# 19.net
KiCad netlist of a schematic drawn in Altium Designer
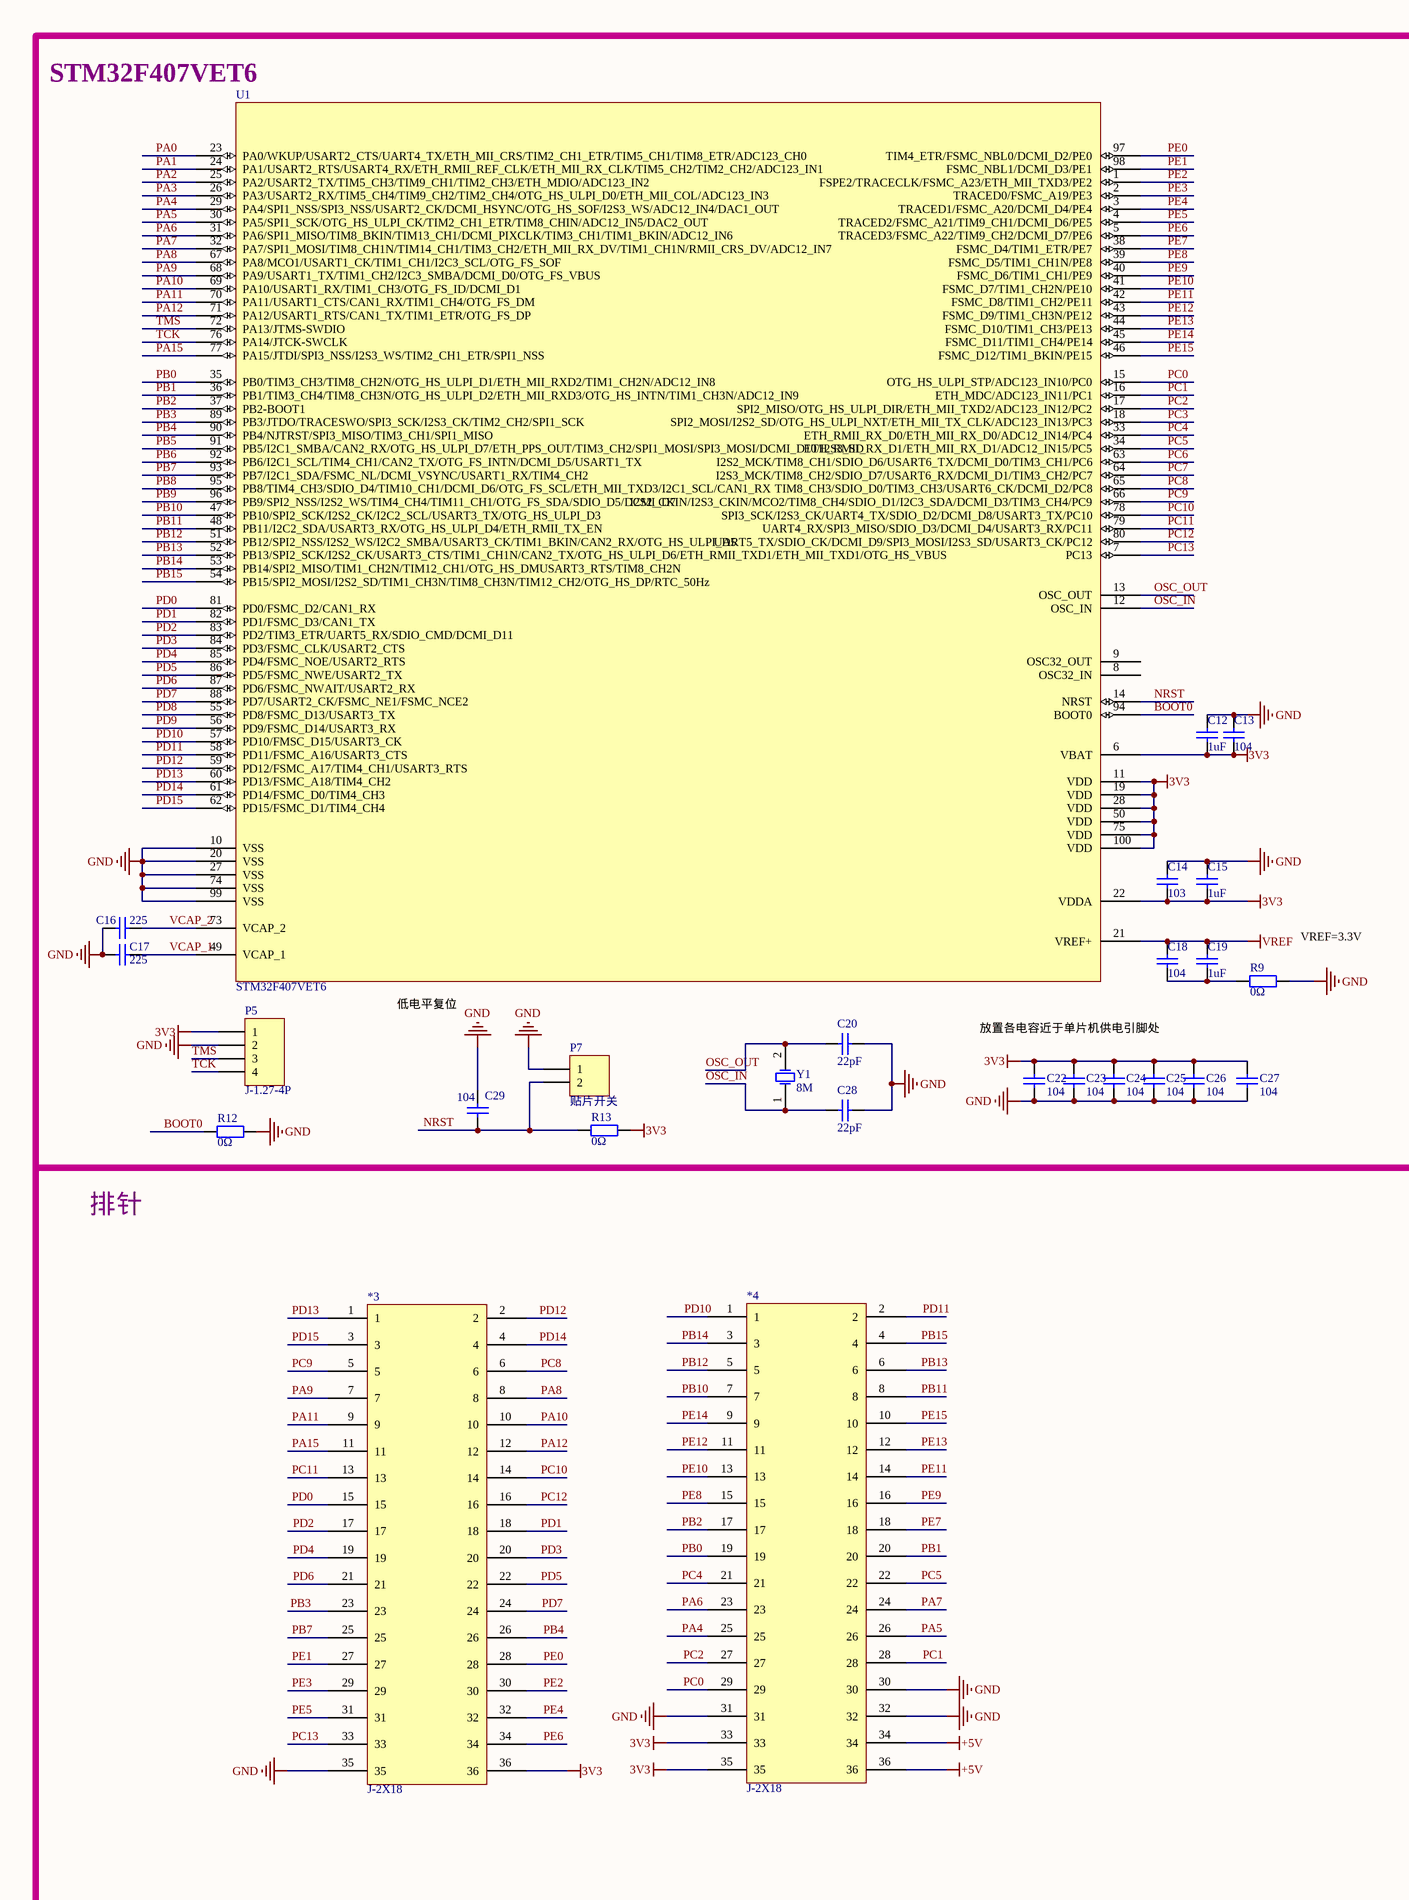
[diagram p0: 19主控.SchDoc, left]
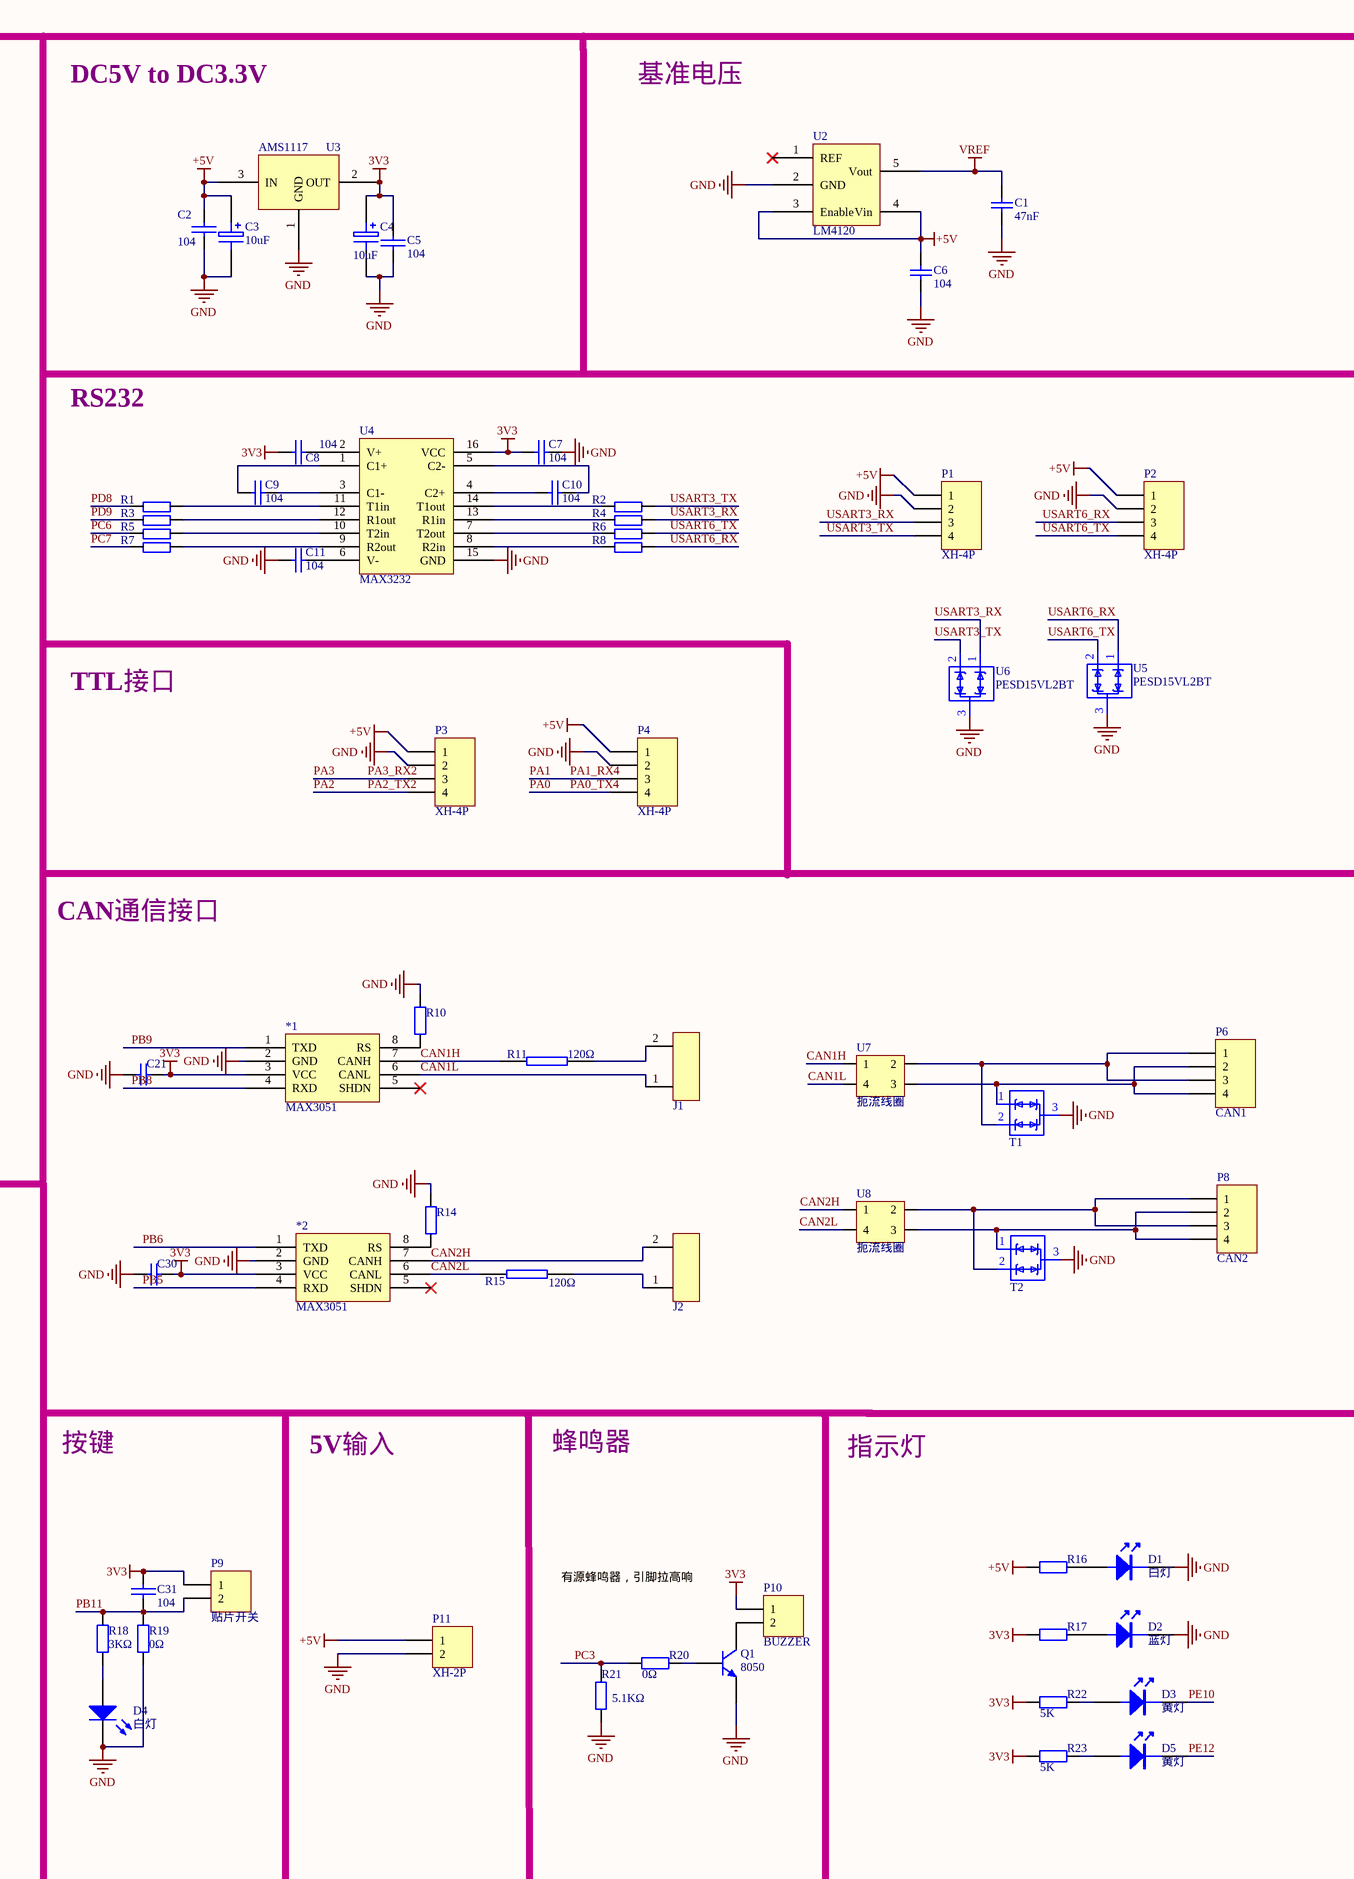
[diagram p1: 19主控.SchDoc, right]

(export (version "E")
  (design (tool "Eeschema 10.0.6"))
  (components
    (comp (ref "*1")
      (value "MAX3051")
      (footprint "SOT-23-8")
      (libsource (lib "ACTION原理图库") (part "MAX3051EKA+T"))
    )
    (comp (ref "*2")
      (value "MAX3051")
      (footprint "SOT-23-8")
      (libsource (lib "ACTION原理图库") (part "MAX3051EKA+T"))
    )
    (comp (ref "*3") (value "J-2X18") (footprint "HDR2X18 排座") (libsource (lib "ACTION原理图库") (part "J-2X18")))
    (comp (ref "*4") (value "J-2X18") (footprint "HDR2X18 排座") (libsource (lib "ACTION原理图库") (part "J-2X18")))
    (comp (ref "C1")
      (value "47nF")
      (footprint "0603_C")
      (description "Capacitor")
      (fields (field (name "PUBLISHER") "Altium Limited"))
      (libsource (lib "Miscellaneous Devices") (part "Cap"))
    )
    (comp (ref "C2")
      (value "104")
      (footprint "0603_C")
      (description "Capacitor")
      (libsource (lib "*") (part "CAP"))
    )
    (comp (ref "C3")
      (value "10uF")
      (footprint "0603_C")
      (description "Electrolytic Capacitor")
      (libsource (lib "*") (part "ELECTRO1"))
    )
    (comp (ref "C4")
      (value "10uF")
      (footprint "0603_C")
      (description "Electrolytic Capacitor")
      (libsource (lib "*") (part "ELECTRO1"))
    )
    (comp (ref "C5")
      (value "104")
      (footprint "0603_C")
      (description "Capacitor")
      (libsource (lib "*") (part "CAP"))
    )
    (comp (ref "C6")
      (value "104")
      (footprint "0603_C")
      (description "Capacitor")
      (fields (field (name "PUBLISHER") "Altium Limited"))
      (libsource (lib "Miscellaneous Devices") (part "Cap"))
    )
    (comp (ref "C7")
      (value "104")
      (footprint "0603_C")
      (description "Capacitor")
      (libsource (lib "*") (part "CAP"))
    )
    (comp (ref "C8")
      (value "104")
      (footprint "0603_C")
      (description "Capacitor")
      (libsource (lib "*") (part "CAP"))
    )
    (comp (ref "C9")
      (value "104")
      (footprint "0603_C")
      (description "Capacitor")
      (libsource (lib "*") (part "CAP"))
    )
    (comp (ref "C10")
      (value "104")
      (footprint "0603_C")
      (description "Capacitor")
      (libsource (lib "*") (part "CAP"))
    )
    (comp (ref "C11")
      (value "104")
      (footprint "0603_C")
      (description "Capacitor")
      (libsource (lib "*") (part "CAP"))
    )
    (comp (ref "C12")
      (value "1uF")
      (footprint "0603_C")
      (description "Capacitor")
      (fields (field (name "PUBLISHER") "Altium Limited"))
      (libsource (lib "Miscellaneous Devices") (part "Cap"))
    )
    (comp (ref "C13")
      (value "104")
      (footprint "0603_C")
      (description "Capacitor")
      (fields (field (name "PUBLISHER") "Altium Limited"))
      (libsource (lib "Miscellaneous Devices") (part "Cap"))
    )
    (comp (ref "C14")
      (value "103")
      (footprint "0603_C")
      (description "Capacitor")
      (fields (field (name "PUBLISHER") "Altium Limited"))
      (libsource (lib "Miscellaneous Devices") (part "Cap"))
    )
    (comp (ref "C15")
      (value "1uF")
      (footprint "0603_C")
      (description "Capacitor")
      (fields (field (name "PUBLISHER") "Altium Limited"))
      (libsource (lib "Miscellaneous Devices") (part "Cap"))
    )
    (comp (ref "C16")
      (value "225")
      (footprint "0603_C")
      (description "Capacitor")
      (fields (field (name "PUBLISHER") "Altium Limited"))
      (libsource (lib "Miscellaneous Devices") (part "Cap"))
    )
    (comp (ref "C17")
      (value "225")
      (footprint "0603_C")
      (description "Capacitor")
      (fields (field (name "PUBLISHER") "Altium Limited"))
      (libsource (lib "Miscellaneous Devices") (part "Cap"))
    )
    (comp (ref "C18")
      (value "104")
      (footprint "0603_C")
      (description "Capacitor")
      (fields (field (name "PUBLISHER") "Altium Limited"))
      (libsource (lib "Miscellaneous Devices") (part "Cap"))
    )
    (comp (ref "C19")
      (value "1uF")
      (footprint "0603_C")
      (description "Capacitor")
      (fields (field (name "PUBLISHER") "Altium Limited"))
      (libsource (lib "Miscellaneous Devices") (part "Cap"))
    )
    (comp (ref "C20")
      (value "22pF")
      (footprint "0603_C")
      (description "Capacitor")
      (fields (field (name "PUBLISHER") "Altium Limited"))
      (libsource (lib "Miscellaneous Devices") (part "Cap"))
    )
    (comp (ref "C21")
      (value "104")
      (footprint "0603_C")
      (description "贴片电容")
      (libsource (lib "Cap0603") (part "0603 100nF (104) 10% 50V"))
    )
    (comp (ref "C22")
      (value "104")
      (footprint "0603_C")
      (description "Capacitor")
      (fields (field (name "PUBLISHER") "Altium Limited"))
      (libsource (lib "Miscellaneous Devices") (part "Cap"))
    )
    (comp (ref "C23")
      (value "104")
      (footprint "0603_C")
      (description "Capacitor")
      (fields (field (name "PUBLISHER") "Altium Limited"))
      (libsource (lib "Miscellaneous Devices") (part "Cap"))
    )
    (comp (ref "C24")
      (value "104")
      (footprint "0603_C")
      (description "Capacitor")
      (fields (field (name "PUBLISHER") "Altium Limited"))
      (libsource (lib "Miscellaneous Devices") (part "Cap"))
    )
    (comp (ref "C25")
      (value "104")
      (footprint "0603_C")
      (description "Capacitor")
      (fields (field (name "PUBLISHER") "Altium Limited"))
      (libsource (lib "Miscellaneous Devices") (part "Cap"))
    )
    (comp (ref "C26")
      (value "104")
      (footprint "0603_C")
      (description "Capacitor")
      (fields (field (name "PUBLISHER") "Altium Limited"))
      (libsource (lib "Miscellaneous Devices") (part "Cap"))
    )
    (comp (ref "C27")
      (value "104")
      (footprint "0603_C")
      (description "Capacitor")
      (fields (field (name "PUBLISHER") "Altium Limited"))
      (libsource (lib "Miscellaneous Devices") (part "Cap"))
    )
    (comp (ref "C28")
      (value "22pF")
      (footprint "0603_C")
      (description "Capacitor")
      (fields (field (name "PUBLISHER") "Altium Limited"))
      (libsource (lib "Miscellaneous Devices") (part "Cap"))
    )
    (comp (ref "C29")
      (value "104")
      (footprint "0603_C")
      (description "Capacitor")
      (fields (field (name "PUBLISHER") "Altium Limited"))
      (libsource (lib "Miscellaneous Devices") (part "Cap"))
    )
    (comp (ref "C30")
      (value "104")
      (footprint "0603_C")
      (description "贴片电容")
      (libsource (lib "Cap0603") (part "0603 100nF (104) 10% 50V"))
    )
    (comp (ref "C31")
      (value "104")
      (footprint "0603_C")
      (description "Capacitor")
      (libsource (lib "*") (part "CAP"))
    )
    (comp (ref "D1") (value "白灯") (footprint "0603_LED_S1") (libsource (lib "Free Documents") (part "LED")))
    (comp (ref "D2") (value "蓝灯") (footprint "0603_LED_S1") (libsource (lib "Free Documents") (part "LED")))
    (comp (ref "D3") (value "黄灯") (footprint "0603_LED_S1") (libsource (lib "Free Documents") (part "LED")))
    (comp (ref "D4")
      (value "白灯")
      (footprint "0603_LED_S1")
      (description "Typical INFRARED GaAs LED")
      (fields (field (name "PUBLISHER") "Altium Limited"))
      (libsource (lib "Miscellaneous Devices") (part "LED0"))
    )
    (comp (ref "D5") (value "黄灯") (footprint "0603_LED_S1") (libsource (lib "Free Documents") (part "LED")))
    (comp (ref "J1")
      (value "拨码开关")
      (footprint "拨码开关贴片1位")
      (description "SOCKET")
      (libsource (lib "ACTION原理图库") (part "J-2PIN"))
    )
    (comp (ref "J2")
      (value "拨码开关")
      (footprint "拨码开关贴片1位")
      (description "SOCKET")
      (libsource (lib "ACTION原理图库") (part "J-2PIN"))
    )
    (comp (ref "P1")
      (value "XH-4P")
      (footprint "J-xh-4AW短")
      (description "Header, 4-Pin")
      (fields (field (name "PUBLISHER") "Altium Limited"))
      (libsource (lib "Miscellaneous Connectors") (part "Header 4"))
    )
    (comp (ref "P2")
      (value "XH-4P")
      (footprint "J-xh-4AW短")
      (description "Header, 4-Pin")
      (fields (field (name "PUBLISHER") "Altium Limited"))
      (libsource (lib "Miscellaneous Connectors") (part "Header 4"))
    )
    (comp (ref "P3")
      (value "XH-4P")
      (footprint "J-xh-4AW短")
      (description "Header, 4-Pin")
      (fields (field (name "PUBLISHER") "Altium Limited"))
      (libsource (lib "Miscellaneous Connectors") (part "Header 4"))
    )
    (comp (ref "P4")
      (value "XH-4P")
      (footprint "J-xh-4AW短")
      (description "Header, 4-Pin")
      (fields (field (name "PUBLISHER") "Altium Limited"))
      (libsource (lib "Miscellaneous Connectors") (part "Header 4"))
    )
    (comp (ref "P5")
      (value "J-1.27-4P")
      (footprint "J-1.27-4P")
      (description "Header, 4-Pin")
      (fields (field (name "PUBLISHER") "Altium Limited"))
      (libsource (lib "Miscellaneous Connectors") (part "Header 4"))
    )
    (comp (ref "P6")
      (value "CAN1")
      (footprint "J-Molex小5557-2*2")
      (description "Header, 4-Pin")
      (fields (field (name "PUBLISHER") "Altium Limited"))
      (libsource (lib "大车主控第二版") (part "Header 4"))
    )
    (comp (ref "P7")
      (value "贴片开关")
      (footprint "按键2脚")
      (description "Header, 2-Pin")
      (fields (field (name "PUBLISHER") "Altium Limited"))
      (libsource (lib "Miscellaneous Connectors") (part "Header 2"))
    )
    (comp (ref "P8")
      (value "CAN2")
      (footprint "J-Molex小5557-2*2")
      (description "Header, 4-Pin")
      (fields (field (name "PUBLISHER") "Altium Limited"))
      (libsource (lib "大车主控第二版") (part "Header 4"))
    )
    (comp (ref "P9")
      (value "贴片开关")
      (footprint "按键2脚")
      (description "Header, 2-Pin")
      (fields (field (name "PUBLISHER") "Altium Limited"))
      (libsource (lib "Miscellaneous Connectors") (part "Header 2"))
    )
    (comp (ref "P10")
      (value "BUZZER")
      (footprint "直插蜂鸣器-9.6mm")
      (description "Header, 2-Pin")
      (fields (field (name "PUBLISHER") "Altium Limited"))
      (libsource (lib "Miscellaneous Connectors") (part "Header 2"))
    )
    (comp (ref "P11")
      (value "XH-2P")
      (footprint "J-XH-2AW短")
      (description "Header, 2-Pin")
      (fields (field (name "PUBLISHER") "Altium Limited"))
      (libsource (lib "Miscellaneous Connectors") (part "Header 2"))
    )
    (comp (ref "Q1")
      (value "8050")
      (footprint "SOT-233")
      (description "NPN General Purpose Amplifier")
      (fields (field (name "PUBLISHER") "Altium Limited"))
      (libsource (lib "大车主控第二版") (part "2N3904"))
    )
    (comp (ref "R1")
      (value "120Ω")
      (footprint "0603_R")
      (description "贴片电阻")
      (libsource (lib "ACTION原理图库") (part "R-贴片电阻 -0603"))
    )
    (comp (ref "R2")
      (value "120Ω")
      (footprint "0603_R")
      (description "贴片电阻")
      (libsource (lib "ACTION原理图库") (part "R-贴片电阻 -0603"))
    )
    (comp (ref "R3")
      (value "120Ω")
      (footprint "0603_R")
      (description "贴片电阻")
      (libsource (lib "ACTION原理图库") (part "R-贴片电阻 -0603"))
    )
    (comp (ref "R4")
      (value "120Ω")
      (footprint "0603_R")
      (description "贴片电阻")
      (libsource (lib "ACTION原理图库") (part "R-贴片电阻 -0603"))
    )
    (comp (ref "R5")
      (value "120Ω")
      (footprint "0603_R")
      (description "贴片电阻")
      (libsource (lib "ACTION原理图库") (part "R-贴片电阻 -0603"))
    )
    (comp (ref "R6")
      (value "120Ω")
      (footprint "0603_R")
      (description "贴片电阻")
      (libsource (lib "ACTION原理图库") (part "R-贴片电阻 -0603"))
    )
    (comp (ref "R7")
      (value "120Ω")
      (footprint "0603_R")
      (description "贴片电阻")
      (libsource (lib "ACTION原理图库") (part "R-贴片电阻 -0603"))
    )
    (comp (ref "R8")
      (value "120Ω")
      (footprint "0603_R")
      (description "贴片电阻")
      (libsource (lib "ACTION原理图库") (part "R-贴片电阻 -0603"))
    )
    (comp (ref "R9")
      (value "0Ω")
      (footprint "R-0603")
      (description "Resistor")
      (fields (field (name "PUBLISHER") "Altium Limited"))
      (libsource (lib "") (part "Res2_2"))
    )
    (comp (ref "R10")
      (value "0Ω")
      (footprint "0603_R")
      (description "贴片电阻")
      (libsource (lib "RES0603") (part "0603 120Ω (1200) 1%"))
    )
    (comp (ref "R11") (value "120Ω") (footprint "0603_R") (libsource (lib "*") (part "RES2")))
    (comp (ref "R12")
      (value "0Ω")
      (footprint "0603_R")
      (description "Resistor")
      (fields (field (name "PUBLISHER") "Altium Limited"))
      (libsource (lib "") (part "Res2_1"))
    )
    (comp (ref "R13")
      (value "0Ω")
      (footprint "0603_R")
      (description "Resistor")
      (fields (field (name "PUBLISHER") "Altium Limited"))
      (libsource (lib "") (part "Res2_1"))
    )
    (comp (ref "R14")
      (value "0Ω")
      (footprint "0603_R")
      (description "贴片电阻")
      (libsource (lib "RES0603") (part "0603 120Ω (1200) 1%"))
    )
    (comp (ref "R15") (value "120Ω") (footprint "0603_R") (libsource (lib "*") (part "RES2")))
    (comp (ref "R16")
      (value "5.1KΩ")
      (footprint "0603_R")
      (description "Resistor")
      (fields (field (name "PUBLISHER") "Altium Limited"))
      (libsource (lib "Free Documents") (part "Res2"))
    )
    (comp (ref "R17")
      (value "0Ω")
      (footprint "0603_R")
      (description "Resistor")
      (fields (field (name "PUBLISHER") "Altium Limited"))
      (libsource (lib "Free Documents") (part "Res2"))
    )
    (comp (ref "R18")
      (value "3KΩ")
      (footprint "0603_R")
      (description "Resistor")
      (libsource (lib "Miscellaneous Devices") (part "Res2"))
    )
    (comp (ref "R19")
      (value "0Ω")
      (footprint "0603_R")
      (description "Resistor")
      (fields (field (name "PUBLISHER") "Altium Limited"))
      (libsource (lib "Miscellaneous Devices") (part "Res2"))
    )
    (comp (ref "R20")
      (value "0Ω")
      (footprint "0603_R")
      (description "Resistor")
      (fields (field (name "PUBLISHER") "Altium Limited"))
      (libsource (lib "") (part "Res2_1"))
    )
    (comp (ref "R21")
      (value "5.1KΩ")
      (footprint "0603_R")
      (description "Resistor")
      (fields (field (name "PUBLISHER") "Altium Limited"))
      (libsource (lib "Miscellaneous Devices") (part "Res2"))
    )
    (comp (ref "R22")
      (value "5K")
      (footprint "0603_R")
      (description "Resistor")
      (fields (field (name "PUBLISHER") "Altium Limited"))
      (libsource (lib "Free Documents") (part "Res2"))
    )
    (comp (ref "R23")
      (value "5K")
      (footprint "0603_R")
      (description "Resistor")
      (fields (field (name "PUBLISHER") "Altium Limited"))
      (libsource (lib "Free Documents") (part "Res2"))
    )
    (comp (ref "T1") (value "双向TVS管") (footprint "SOT-233") (libsource (lib "ACTION原理图库") (part "双向TVS管")))
    (comp (ref "T2") (value "双向TVS管") (footprint "SOT-233") (libsource (lib "ACTION原理图库") (part "双向TVS管")))
    (comp (ref "U1")
      (value "STM32F407VET6")
      (footprint "LQFP-100_14x14x05P")
      (libsource (lib "action") (part "STM32F407VET6"))
    )
    (comp (ref "U2") (value "LM4120") (footprint "SOT-235") (libsource (lib "bq76925") (part "LM4120")))
    (comp (ref "U3") (value "AMS1117") (footprint "sot-223") (libsource (lib "*") (part "Component_1")))
    (comp (ref "U4") (value "MAX3232") (footprint "SSOP-16") (libsource (lib "action") (part "MAX3232")))
    (comp (ref "U5")
      (value "PESD15VL2BT")
      (footprint "SOT-233")
      (libsource (lib "ACTION原理图库") (part "PESD2CAN"))
    )
    (comp (ref "U6")
      (value "PESD15VL2BT")
      (footprint "SOT-233")
      (libsource (lib "ACTION原理图库") (part "PESD2CAN"))
    )
    (comp (ref "U7")
      (value "扼流线圈")
      (footprint "共模电感ACT45B-2P")
      (description "B82793C0/S0")
      (libsource (lib "ACTION原理图库") (part "扼流线圈"))
    )
    (comp (ref "U8")
      (value "扼流线圈")
      (footprint "共模电感ACT45B-2P")
      (description "B82793C0/S0")
      (libsource (lib "ACTION原理图库") (part "扼流线圈"))
    )
    (comp (ref "Y1")
      (value "8M")
      (footprint "X-HC49S")
      (description "Crystal Oscillator")
      (fields (field (name "PUBLISHER") "Altium Limited"))
      (libsource (lib "Miscellaneous Devices") (part "XTAL"))
    )
  )
  (nets
    (net (code "1") (name "+5V") (class "Default")
      (node (ref "*4") (pin "34") (pinfunction "34_34") (pintype "passive"))
      (node (ref "*4") (pin "36") (pinfunction "36_36") (pintype "passive"))
      (node (ref "C2") (pin "1") (pinfunction "1_1") (pintype "passive"))
      (node (ref "C3") (pin "1") (pinfunction "1_1") (pintype "passive"))
      (node (ref "C6") (pin "2") (pinfunction "2_2") (pintype "passive"))
      (node (ref "P1") (pin "1") (pinfunction "1_1") (pintype "passive"))
      (node (ref "P11") (pin "1") (pinfunction "1_1") (pintype "passive"))
      (node (ref "P2") (pin "1") (pinfunction "1_1") (pintype "passive"))
      (node (ref "P3") (pin "1") (pinfunction "1_1") (pintype "passive"))
      (node (ref "P4") (pin "1") (pinfunction "1_1") (pintype "passive"))
      (node (ref "R16") (pin "1") (pinfunction "1_1") (pintype "passive"))
      (node (ref "U2") (pin "3") (pinfunction "Enable_3") (pintype "passive"))
      (node (ref "U2") (pin "4") (pinfunction "Vin_4") (pintype "passive"))
      (node (ref "U3") (pin "3") (pinfunction "IN_3") (pintype "passive"))
    )
    (net (code "2") (name "/BOOT0") (class "Default")
      (node (ref "R12") (pin "1") (pinfunction "1_1") (pintype "passive"))
      (node (ref "U1") (pin "94") (pinfunction "BOOT0_94") (pintype "bidirectional"))
    )
    (net (code "3") (name "/CAN1H") (class "Default")
      (node (ref "*1") (pin "7") (pinfunction "CANH_7") (pintype "passive"))
      (node (ref "R11") (pin "2") (pinfunction "2_2") (pintype "passive"))
      (node (ref "U7") (pin "1") (pinfunction "1_1") (pintype "passive"))
    )
    (net (code "4") (name "/CAN1L") (class "Default")
      (node (ref "*1") (pin "6") (pinfunction "CANL_6") (pintype "passive"))
      (node (ref "J1") (pin "1") (pinfunction "1_1") (pintype "passive"))
      (node (ref "U7") (pin "4") (pinfunction "4_4") (pintype "passive"))
    )
    (net (code "5") (name "/CAN2H") (class "Default")
      (node (ref "*2") (pin "7") (pinfunction "CANH_7") (pintype "passive"))
      (node (ref "J2") (pin "2") (pinfunction "2_2") (pintype "passive"))
      (node (ref "U8") (pin "1") (pinfunction "1_1") (pintype "passive"))
    )
    (net (code "6") (name "/CAN2L") (class "Default")
      (node (ref "*2") (pin "6") (pinfunction "CANL_6") (pintype "passive"))
      (node (ref "R15") (pin "2") (pinfunction "2_2") (pintype "passive"))
      (node (ref "U8") (pin "4") (pinfunction "4_4") (pintype "passive"))
    )
    (net (code "7") (name "/NRST") (class "Default")
      (node (ref "C29") (pin "1") (pinfunction "1_1") (pintype "passive"))
      (node (ref "P7") (pin "2") (pinfunction "2_2") (pintype "passive"))
      (node (ref "R13") (pin "1") (pinfunction "1_1") (pintype "passive"))
      (node (ref "U1") (pin "14") (pinfunction "NRST_14") (pintype "bidirectional"))
    )
    (net (code "8") (name "/OSC_IN") (class "Default")
      (node (ref "C28") (pin "1") (pinfunction "1_1") (pintype "passive"))
      (node (ref "U1") (pin "12") (pinfunction "OSC_IN_12") (pintype "passive"))
      (node (ref "Y1") (pin "1") (pinfunction "OSC1_1") (pintype "passive"))
    )
    (net (code "9") (name "/OSC_OUT") (class "Default")
      (node (ref "C20") (pin "1") (pinfunction "1_1") (pintype "passive"))
      (node (ref "U1") (pin "13") (pinfunction "OSC_OUT_13") (pintype "passive"))
      (node (ref "Y1") (pin "2") (pinfunction "OSC2_2") (pintype "passive"))
    )
    (net (code "10") (name "/PA0") (class "Default")
      (node (ref "P4") (pin "4") (pinfunction "4_4") (pintype "passive"))
      (node (ref "U1") (pin "23") (pinfunction "PA0/WKUP/USART2_CTS/UART4_TX/ETH_MII_CRS/TIM2_CH1_ETR/TIM5_CH1/TIM8_ETR/ADC123_CH0_23") (pintype "bidirectional"))
    )
    (net (code "11") (name "/PA1") (class "Default")
      (node (ref "P4") (pin "3") (pinfunction "3_3") (pintype "passive"))
      (node (ref "U1") (pin "24") (pinfunction "PA1/USART2_RTS/USART4_RX/ETH_RMII_REF_CLK/ETH_MII_RX_CLK/TIM5_CH2/TIM2_CH2/ADC123_IN1_24") (pintype "bidirectional"))
    )
    (net (code "12") (name "/PA2") (class "Default")
      (node (ref "P3") (pin "4") (pinfunction "4_4") (pintype "passive"))
      (node (ref "U1") (pin "25") (pinfunction "PA2/USART2_TX/TIM5_CH3/TIM9_CH1/TIM2_CH3/ETH_MDIO/ADC123_IN2_25") (pintype "bidirectional"))
    )
    (net (code "13") (name "/PA3") (class "Default")
      (node (ref "P3") (pin "3") (pinfunction "3_3") (pintype "passive"))
      (node (ref "U1") (pin "26") (pinfunction "PA3/USART2_RX/TIM5_CH4/TIM9_CH2/TIM2_CH4/OTG_HS_ULPI_D0/ETH_MII_COL/ADC123_IN3_26") (pintype "bidirectional"))
    )
    (net (code "14") (name "/PA4") (class "Default")
      (node (ref "*4") (pin "25") (pinfunction "25_25") (pintype "passive"))
      (node (ref "U1") (pin "29") (pinfunction "PA4/SPI1_NSS/SPI3_NSS/USART2_CK/DCMI_HSYNC/OTG_HS_SOF/I2S3_WS/ADC12_IN4/DAC1_OUT_29") (pintype "bidirectional"))
    )
    (net (code "15") (name "/PA5") (class "Default")
      (node (ref "*4") (pin "26") (pinfunction "26_26") (pintype "passive"))
      (node (ref "U1") (pin "30") (pinfunction "PA5/SPI1_SCK/OTG_HS_ULPI_CK/TIM2_CH1_ETR/TIM8_CHIN/ADC12_IN5/DAC2_OUT_30") (pintype "bidirectional"))
    )
    (net (code "16") (name "/PA6") (class "Default")
      (node (ref "*4") (pin "23") (pinfunction "23_23") (pintype "passive"))
      (node (ref "U1") (pin "31") (pinfunction "PA6/SPI1_MISO/TIM8_BKIN/TIM13_CH1/DCMI_PIXCLK/TIM3_CH1/TIM1_BKIN/ADC12_IN6_31") (pintype "bidirectional"))
    )
    (net (code "17") (name "/PA7") (class "Default")
      (node (ref "*4") (pin "24") (pinfunction "24_24") (pintype "passive"))
      (node (ref "U1") (pin "32") (pinfunction "PA7/SPI1_MOSI/TIM8_CH1N/TIM14_CH1/TIM3_CH2/ETH_MII_RX_DV/TIM1_CH1N/RMII_CRS_DV/ADC12_IN7_32") (pintype "bidirectional"))
    )
    (net (code "18") (name "/PA8") (class "Default")
      (node (ref "*3") (pin "8") (pinfunction "8_8") (pintype "passive"))
      (node (ref "U1") (pin "67") (pinfunction "PA8/MCO1/USART1_CK/TIM1_CH1/I2C3_SCL/OTG_FS_SOF_67") (pintype "bidirectional"))
    )
    (net (code "19") (name "/PA9") (class "Default")
      (node (ref "*3") (pin "7") (pinfunction "7_7") (pintype "passive"))
      (node (ref "U1") (pin "68") (pinfunction "PA9/USART1_TX/TIM1_CH2/I2C3_SMBA/DCMI_D0/OTG_FS_VBUS_68") (pintype "bidirectional"))
    )
    (net (code "20") (name "/PA10") (class "Default")
      (node (ref "*3") (pin "10") (pinfunction "10_10") (pintype "passive"))
      (node (ref "U1") (pin "69") (pinfunction "PA10/USART1_RX/TIM1_CH3/OTG_FS_ID/DCMI_D1_69") (pintype "bidirectional"))
    )
    (net (code "21") (name "/PA11") (class "Default")
      (node (ref "*3") (pin "9") (pinfunction "9_9") (pintype "passive"))
      (node (ref "U1") (pin "70") (pinfunction "PA11/USART1_CTS/CAN1_RX/TIM1_CH4/OTG_FS_DM_70") (pintype "bidirectional"))
    )
    (net (code "22") (name "/PA12") (class "Default")
      (node (ref "*3") (pin "12") (pinfunction "12_12") (pintype "passive"))
      (node (ref "U1") (pin "71") (pinfunction "PA12/USART1_RTS/CAN1_TX/TIM1_ETR/OTG_FS_DP_71") (pintype "bidirectional"))
    )
    (net (code "23") (name "/PA15") (class "Default")
      (node (ref "*3") (pin "11") (pinfunction "11_11") (pintype "passive"))
      (node (ref "U1") (pin "77") (pinfunction "PA15/JTDI/SPI3_NSS/I2S3_WS/TIM2_CH1_ETR/SPI1_NSS_77") (pintype "bidirectional"))
    )
    (net (code "24") (name "/PB0") (class "Default")
      (node (ref "*4") (pin "19") (pinfunction "19_19") (pintype "passive"))
      (node (ref "U1") (pin "35") (pinfunction "PB0/TIM3_CH3/TIM8_CH2N/OTG_HS_ULPI_D1/ETH_MII_RXD2/TIM1_CH2N/ADC12_IN8_35") (pintype "bidirectional"))
    )
    (net (code "25") (name "/PB1") (class "Default")
      (node (ref "*4") (pin "20") (pinfunction "20_20") (pintype "passive"))
      (node (ref "U1") (pin "36") (pinfunction "PB1/TIM3_CH4/TIM8_CH3N/OTG_HS_ULPI_D2/ETH_MII_RXD3/OTG_HS_INTN/TIM1_CH3N/ADC12_IN9_36") (pintype "bidirectional"))
    )
    (net (code "26") (name "/PB2") (class "Default")
      (node (ref "*4") (pin "17") (pinfunction "17_17") (pintype "passive"))
      (node (ref "U1") (pin "37") (pinfunction "PB2-BOOT1_37") (pintype "bidirectional"))
    )
    (net (code "27") (name "/PB3") (class "Default")
      (node (ref "*3") (pin "23") (pinfunction "23_23") (pintype "passive"))
      (node (ref "U1") (pin "89") (pinfunction "PB3/JTDO/TRACESWO/SPI3_SCK/I2S3_CK/TIM2_CH2/SPI1_SCK_89") (pintype "bidirectional"))
    )
    (net (code "28") (name "/PB4") (class "Default")
      (node (ref "*3") (pin "26") (pinfunction "26_26") (pintype "passive"))
      (node (ref "U1") (pin "90") (pinfunction "PB4/NJTRST/SPI3_MISO/TIM3_CH1/SPI1_MISO_90") (pintype "bidirectional"))
    )
    (net (code "29") (name "/PB5") (class "Default")
      (node (ref "*2") (pin "4") (pinfunction "RXD_4") (pintype "passive"))
      (node (ref "U1") (pin "91") (pinfunction "PB5/I2C1_SMBA/CAN2_RX/OTG_HS_ULPI_D7/ETH_PPS_OUT/TIM3_CH2/SPI1_MOSI/SPI3_MOSI/DCMI_D10/I2S3_SD_91") (pintype "bidirectional"))
    )
    (net (code "30") (name "/PB6") (class "Default")
      (node (ref "*2") (pin "1") (pinfunction "TXD_1") (pintype "passive"))
      (node (ref "U1") (pin "92") (pinfunction "PB6/I2C1_SCL/TIM4_CH1/CAN2_TX/OTG_FS_INTN/DCMI_D5/USART1_TX_92") (pintype "bidirectional"))
    )
    (net (code "31") (name "/PB7") (class "Default")
      (node (ref "*3") (pin "25") (pinfunction "25_25") (pintype "passive"))
      (node (ref "U1") (pin "93") (pinfunction "PB7/I2C1_SDA/FSMC_NL/DCMI_VSYNC/USART1_RX/TIM4_CH2_93") (pintype "bidirectional"))
    )
    (net (code "32") (name "/PB8") (class "Default")
      (node (ref "*1") (pin "4") (pinfunction "RXD_4") (pintype "passive"))
      (node (ref "U1") (pin "95") (pinfunction "PB8/TIM4_CH3/SDIO_D4/TIM10_CH1/DCMI_D6/OTG_FS_SCL/ETH_MII_TXD3/I2C1_SCL/CAN1_RX_95") (pintype "bidirectional"))
    )
    (net (code "33") (name "/PB9") (class "Default")
      (node (ref "*1") (pin "1") (pinfunction "TXD_1") (pintype "passive"))
      (node (ref "U1") (pin "96") (pinfunction "PB9/SPI2_NSS/I2S2_WS/TIM4_CH4/TIM11_CH1/OTG_FS_SDA/SDIO_D5/DCMI_D7_96") (pintype "bidirectional"))
    )
    (net (code "34") (name "/PB10") (class "Default")
      (node (ref "*4") (pin "7") (pinfunction "7_7") (pintype "passive"))
      (node (ref "U1") (pin "47") (pinfunction "PB10/SPI2_SCK/I2S2_CK/I2C2_SCL/USART3_TX/OTG_HS_ULPI_D3_47") (pintype "bidirectional"))
    )
    (net (code "35") (name "/PB11") (class "Default")
      (node (ref "*4") (pin "8") (pinfunction "8_8") (pintype "passive"))
      (node (ref "C31") (pin "2") (pinfunction "2_2") (pintype "passive"))
      (node (ref "P9") (pin "2") (pinfunction "2_2") (pintype "passive"))
      (node (ref "R18") (pin "2") (pinfunction "2_2") (pintype "passive"))
      (node (ref "R19") (pin "2") (pinfunction "2_2") (pintype "passive"))
      (node (ref "U1") (pin "48") (pinfunction "PB11/I2C2_SDA/USART3_RX/OTG_HS_ULPI_D4/ETH_RMII_TX_EN_48") (pintype "bidirectional"))
    )
    (net (code "36") (name "/PB12") (class "Default")
      (node (ref "*4") (pin "5") (pinfunction "5_5") (pintype "passive"))
      (node (ref "U1") (pin "51") (pinfunction "PB12/SPI2_NSS/I2S2_WS/I2C2_SMBA/USART3_CK/TIM1_BKIN/CAN2_RX/OTG_HS_ULPI_D5_51") (pintype "bidirectional"))
    )
    (net (code "37") (name "/PB13") (class "Default")
      (node (ref "*4") (pin "6") (pinfunction "6_6") (pintype "passive"))
      (node (ref "U1") (pin "52") (pinfunction "PB13/SPI2_SCK/I2S2_CK/USART3_CTS/TIM1_CH1N/CAN2_TX/OTG_HS_ULPI_D6/ETH_RMII_TXD1/ETH_MII_TXD1/OTG_HS_VBUS_52") (pintype "bidirectional"))
    )
    (net (code "38") (name "/PB14") (class "Default")
      (node (ref "*4") (pin "3") (pinfunction "3_3") (pintype "passive"))
      (node (ref "U1") (pin "53") (pinfunction "PB14/SPI2_MISO/TIM1_CH2N/TIM12_CH1/OTG_HS_DMUSART3_RTS/TIM8_CH2N_53") (pintype "bidirectional"))
    )
    (net (code "39") (name "/PB15") (class "Default")
      (node (ref "*4") (pin "4") (pinfunction "4_4") (pintype "passive"))
      (node (ref "U1") (pin "54") (pinfunction "PB15/SPI2_MOSI/I2S2_SD/TIM1_CH3N/TIM8_CH3N/TIM12_CH2/OTG_HS_DP/RTC_50Hz_54") (pintype "bidirectional"))
    )
    (net (code "40") (name "/PC0") (class "Default")
      (node (ref "*4") (pin "29") (pinfunction "29_29") (pintype "passive"))
      (node (ref "U1") (pin "15") (pinfunction "OTG_HS_ULPI_STP/ADC123_IN10/PC0_15") (pintype "bidirectional"))
    )
    (net (code "41") (name "/PC1") (class "Default")
      (node (ref "*4") (pin "28") (pinfunction "28_28") (pintype "passive"))
      (node (ref "U1") (pin "16") (pinfunction "ETH_MDC/ADC123_IN11/PC1_16") (pintype "bidirectional"))
    )
    (net (code "42") (name "/PC2") (class "Default")
      (node (ref "*4") (pin "27") (pinfunction "27_27") (pintype "passive"))
      (node (ref "U1") (pin "17") (pinfunction "SPI2_MISO/OTG_HS_ULPI_DIR/ETH_MII_TXD2/ADC123_IN12/PC2_17") (pintype "bidirectional"))
    )
    (net (code "43") (name "/PC3") (class "Default")
      (node (ref "R20") (pin "1") (pinfunction "1_1") (pintype "passive"))
      (node (ref "R21") (pin "2") (pinfunction "2_2") (pintype "passive"))
      (node (ref "U1") (pin "18") (pinfunction "SPI2_MOSI/I2S2_SD/OTG_HS_ULPI_NXT/ETH_MII_TX_CLK/ADC123_IN13/PC3_18") (pintype "bidirectional"))
    )
    (net (code "44") (name "/PC4") (class "Default")
      (node (ref "*4") (pin "21") (pinfunction "21_21") (pintype "passive"))
      (node (ref "U1") (pin "33") (pinfunction "ETH_RMII_RX_D0/ETH_MII_RX_D0/ADC12_IN14/PC4_33") (pintype "bidirectional"))
    )
    (net (code "45") (name "/PC5") (class "Default")
      (node (ref "*4") (pin "22") (pinfunction "22_22") (pintype "passive"))
      (node (ref "U1") (pin "34") (pinfunction "ETH_RMII_RX_D1/ETH_MII_RX_D1/ADC12_IN15/PC5_34") (pintype "bidirectional"))
    )
    (net (code "46") (name "/PC6") (class "Default")
      (node (ref "R5") (pin "1") (pintype "passive"))
      (node (ref "U1") (pin "63") (pinfunction "I2S2_MCK/TIM8_CH1/SDIO_D6/USART6_TX/DCMI_D0/TIM3_CH1/PC6_63") (pintype "bidirectional"))
    )
    (net (code "47") (name "/PC7") (class "Default")
      (node (ref "R7") (pin "1") (pintype "passive"))
      (node (ref "U1") (pin "64") (pinfunction "I2S3_MCK/TIM8_CH2/SDIO_D7/USART6_RX/DCMI_D1/TIM3_CH2/PC7_64") (pintype "bidirectional"))
    )
    (net (code "48") (name "/PC8") (class "Default")
      (node (ref "*3") (pin "6") (pinfunction "6_6") (pintype "passive"))
      (node (ref "U1") (pin "65") (pinfunction "TIM8_CH3/SDIO_D0/TIM3_CH3/USART6_CK/DCMI_D2/PC8_65") (pintype "bidirectional"))
    )
    (net (code "49") (name "/PC9") (class "Default")
      (node (ref "*3") (pin "5") (pinfunction "5_5") (pintype "passive"))
      (node (ref "U1") (pin "66") (pinfunction "I2S2_CKIN/I2S3_CKIN/MCO2/TIM8_CH4/SDIO_D1/I2C3_SDA/DCMI_D3/TIM3_CH4/PC9_66") (pintype "bidirectional"))
    )
    (net (code "50") (name "/PC10") (class "Default")
      (node (ref "*3") (pin "14") (pinfunction "14_14") (pintype "passive"))
      (node (ref "U1") (pin "78") (pinfunction "SPI3_SCK/I2S3_CK/UART4_TX/SDIO_D2/DCMI_D8/USART3_TX/PC10_78") (pintype "bidirectional"))
    )
    (net (code "51") (name "/PC11") (class "Default")
      (node (ref "*3") (pin "13") (pinfunction "13_13") (pintype "passive"))
      (node (ref "U1") (pin "79") (pinfunction "UART4_RX/SPI3_MISO/SDIO_D3/DCMI_D4/USART3_RX/PC11_79") (pintype "bidirectional"))
    )
    (net (code "52") (name "/PC12") (class "Default")
      (node (ref "*3") (pin "16") (pinfunction "16_16") (pintype "passive"))
      (node (ref "U1") (pin "80") (pinfunction "UART5_TX/SDIO_CK/DCMI_D9/SPI3_MOSI/I2S3_SD/USART3_CK/PC12_80") (pintype "bidirectional"))
    )
    (net (code "53") (name "/PC13") (class "Default")
      (node (ref "*3") (pin "33") (pinfunction "33_33") (pintype "passive"))
      (node (ref "U1") (pin "7") (pinfunction "PC13_7") (pintype "bidirectional"))
    )
    (net (code "54") (name "/PD0") (class "Default")
      (node (ref "*3") (pin "15") (pinfunction "15_15") (pintype "passive"))
      (node (ref "U1") (pin "81") (pinfunction "PD0/FSMC_D2/CAN1_RX_81") (pintype "bidirectional"))
    )
    (net (code "55") (name "/PD1") (class "Default")
      (node (ref "*3") (pin "18") (pinfunction "18_18") (pintype "passive"))
      (node (ref "U1") (pin "82") (pinfunction "PD1/FSMC_D3/CAN1_TX_82") (pintype "bidirectional"))
    )
    (net (code "56") (name "/PD2") (class "Default")
      (node (ref "*3") (pin "17") (pinfunction "17_17") (pintype "passive"))
      (node (ref "U1") (pin "83") (pinfunction "PD2/TIM3_ETR/UART5_RX/SDIO_CMD/DCMI_D11_83") (pintype "bidirectional"))
    )
    (net (code "57") (name "/PD3") (class "Default")
      (node (ref "*3") (pin "20") (pinfunction "20_20") (pintype "passive"))
      (node (ref "U1") (pin "84") (pinfunction "PD3/FSMC_CLK/USART2_CTS_84") (pintype "bidirectional"))
    )
    (net (code "58") (name "/PD4") (class "Default")
      (node (ref "*3") (pin "19") (pinfunction "19_19") (pintype "passive"))
      (node (ref "U1") (pin "85") (pinfunction "PD4/FSMC_NOE/USART2_RTS_85") (pintype "bidirectional"))
    )
    (net (code "59") (name "/PD5") (class "Default")
      (node (ref "*3") (pin "22") (pinfunction "22_22") (pintype "passive"))
      (node (ref "U1") (pin "86") (pinfunction "PD5/FSMC_NWE/USART2_TX_86") (pintype "bidirectional"))
    )
    (net (code "60") (name "/PD6") (class "Default")
      (node (ref "*3") (pin "21") (pinfunction "21_21") (pintype "passive"))
      (node (ref "U1") (pin "87") (pinfunction "PD6/FSMC_NWAIT/USART2_RX_87") (pintype "bidirectional"))
    )
    (net (code "61") (name "/PD7") (class "Default")
      (node (ref "*3") (pin "24") (pinfunction "24_24") (pintype "passive"))
      (node (ref "U1") (pin "88") (pinfunction "PD7/USART2_CK/FSMC_NE1/FSMC_NCE2_88") (pintype "bidirectional"))
    )
    (net (code "62") (name "/PD8") (class "Default")
      (node (ref "R1") (pin "1") (pintype "passive"))
      (node (ref "U1") (pin "55") (pinfunction "PD8/FSMC_D13/USART3_TX_55") (pintype "bidirectional"))
    )
    (net (code "63") (name "/PD9") (class "Default")
      (node (ref "R3") (pin "1") (pintype "passive"))
      (node (ref "U1") (pin "56") (pinfunction "PD9/FSMC_D14/USART3_RX_56") (pintype "bidirectional"))
    )
    (net (code "64") (name "/PD10") (class "Default")
      (node (ref "*4") (pin "1") (pinfunction "1_1") (pintype "passive"))
      (node (ref "U1") (pin "57") (pinfunction "PD10/FMSC_D15/USART3_CK_57") (pintype "bidirectional"))
    )
    (net (code "65") (name "/PD11") (class "Default")
      (node (ref "*4") (pin "2") (pinfunction "2_2") (pintype "passive"))
      (node (ref "U1") (pin "58") (pinfunction "PD11/FSMC_A16/USART3_CTS_58") (pintype "bidirectional"))
    )
    (net (code "66") (name "/PD12") (class "Default")
      (node (ref "*3") (pin "2") (pinfunction "2_2") (pintype "passive"))
      (node (ref "U1") (pin "59") (pinfunction "PD12/FSMC_A17/TIM4_CH1/USART3_RTS_59") (pintype "bidirectional"))
    )
    (net (code "67") (name "/PD13") (class "Default")
      (node (ref "*3") (pin "1") (pinfunction "1_1") (pintype "passive"))
      (node (ref "U1") (pin "60") (pinfunction "PD13/FSMC_A18/TIM4_CH2_60") (pintype "bidirectional"))
    )
    (net (code "68") (name "/PD14") (class "Default")
      (node (ref "*3") (pin "4") (pinfunction "4_4") (pintype "passive"))
      (node (ref "U1") (pin "61") (pinfunction "PD14/FSMC_D0/TIM4_CH3_61") (pintype "bidirectional"))
    )
    (net (code "69") (name "/PD15") (class "Default")
      (node (ref "*3") (pin "3") (pinfunction "3_3") (pintype "passive"))
      (node (ref "U1") (pin "62") (pinfunction "PD15/FSMC_D1/TIM4_CH4_62") (pintype "bidirectional"))
    )
    (net (code "70") (name "/PE0") (class "Default")
      (node (ref "*3") (pin "28") (pinfunction "28_28") (pintype "passive"))
      (node (ref "U1") (pin "97") (pinfunction "TIM4_ETR/FSMC_NBL0/DCMI_D2/PE0_97") (pintype "bidirectional"))
    )
    (net (code "71") (name "/PE1") (class "Default")
      (node (ref "*3") (pin "27") (pinfunction "27_27") (pintype "passive"))
      (node (ref "U1") (pin "98") (pinfunction "FSMC_NBL1/DCMI_D3/PE1_98") (pintype "bidirectional"))
    )
    (net (code "72") (name "/PE2") (class "Default")
      (node (ref "*3") (pin "30") (pinfunction "30_30") (pintype "passive"))
      (node (ref "U1") (pin "1") (pinfunction "FSPE2/TRACECLK/FSMC_A23/ETH_MII_TXD3/PE2_1") (pintype "bidirectional"))
    )
    (net (code "73") (name "/PE3") (class "Default")
      (node (ref "*3") (pin "29") (pinfunction "29_29") (pintype "passive"))
      (node (ref "U1") (pin "2") (pinfunction "TRACED0/FSMC_A19/PE3_2") (pintype "bidirectional"))
    )
    (net (code "74") (name "/PE4") (class "Default")
      (node (ref "*3") (pin "32") (pinfunction "32_32") (pintype "passive"))
      (node (ref "U1") (pin "3") (pinfunction "TRACED1/FSMC_A20/DCMI_D4/PE4_3") (pintype "bidirectional"))
    )
    (net (code "75") (name "/PE5") (class "Default")
      (node (ref "*3") (pin "31") (pinfunction "31_31") (pintype "passive"))
      (node (ref "U1") (pin "4") (pinfunction "TRACED2/FSMC_A21/TIM9_CH1/DCMI_D6/PE5_4") (pintype "bidirectional"))
    )
    (net (code "76") (name "/PE6") (class "Default")
      (node (ref "*3") (pin "34") (pinfunction "34_34") (pintype "passive"))
      (node (ref "U1") (pin "5") (pinfunction "TRACED3/FSMC_A22/TIM9_CH2/DCMI_D7/PE6_5") (pintype "bidirectional"))
    )
    (net (code "77") (name "/PE7") (class "Default")
      (node (ref "*4") (pin "18") (pinfunction "18_18") (pintype "passive"))
      (node (ref "U1") (pin "38") (pinfunction "FSMC_D4/TIM1_ETR/PE7_38") (pintype "bidirectional"))
    )
    (net (code "78") (name "/PE8") (class "Default")
      (node (ref "*4") (pin "15") (pinfunction "15_15") (pintype "passive"))
      (node (ref "U1") (pin "39") (pinfunction "FSMC_D5/TIM1_CH1N/PE8_39") (pintype "bidirectional"))
    )
    (net (code "79") (name "/PE9") (class "Default")
      (node (ref "*4") (pin "16") (pinfunction "16_16") (pintype "passive"))
      (node (ref "U1") (pin "40") (pinfunction "FSMC_D6/TIM1_CH1/PE9_40") (pintype "bidirectional"))
    )
    (net (code "80") (name "/PE10") (class "Default")
      (node (ref "*4") (pin "13") (pinfunction "13_13") (pintype "passive"))
      (node (ref "D3") (pin "K") (pinfunction "2_K") (pintype "passive"))
      (node (ref "U1") (pin "41") (pinfunction "FSMC_D7/TIM1_CH2N/PE10_41") (pintype "bidirectional"))
    )
    (net (code "81") (name "/PE11") (class "Default")
      (node (ref "*4") (pin "14") (pinfunction "14_14") (pintype "passive"))
      (node (ref "U1") (pin "42") (pinfunction "FSMC_D8/TIM1_CH2/PE11_42") (pintype "bidirectional"))
    )
    (net (code "82") (name "/PE12") (class "Default")
      (node (ref "*4") (pin "11") (pinfunction "11_11") (pintype "passive"))
      (node (ref "D5") (pin "K") (pinfunction "2_K") (pintype "passive"))
      (node (ref "U1") (pin "43") (pinfunction "FSMC_D9/TIM1_CH3N/PE12_43") (pintype "bidirectional"))
    )
    (net (code "83") (name "/PE13") (class "Default")
      (node (ref "*4") (pin "12") (pinfunction "12_12") (pintype "passive"))
      (node (ref "U1") (pin "44") (pinfunction "FSMC_D10/TIM1_CH3/PE13_44") (pintype "bidirectional"))
    )
    (net (code "84") (name "/PE14") (class "Default")
      (node (ref "*4") (pin "9") (pinfunction "9_9") (pintype "passive"))
      (node (ref "U1") (pin "45") (pinfunction "FSMC_D11/TIM1_CH4/PE14_45") (pintype "bidirectional"))
    )
    (net (code "85") (name "/PE15") (class "Default")
      (node (ref "*4") (pin "10") (pinfunction "10_10") (pintype "passive"))
      (node (ref "U1") (pin "46") (pinfunction "FSMC_D12/TIM1_BKIN/PE15_46") (pintype "bidirectional"))
    )
    (net (code "86") (name "/TCK") (class "Default")
      (node (ref "P5") (pin "4") (pinfunction "4_4") (pintype "passive"))
      (node (ref "U1") (pin "76") (pinfunction "PA14/JTCK-SWCLK_76") (pintype "bidirectional"))
    )
    (net (code "87") (name "/TMS") (class "Default")
      (node (ref "P5") (pin "3") (pinfunction "3_3") (pintype "passive"))
      (node (ref "U1") (pin "72") (pinfunction "PA13/JTMS-SWDIO_72") (pintype "bidirectional"))
    )
    (net (code "88") (name "/USART3_RX") (class "Default")
      (node (ref "P1") (pin "3") (pinfunction "3_3") (pintype "passive"))
      (node (ref "R4") (pin "2") (pintype "passive"))
      (node (ref "U6") (pin "1") (pinfunction "1_1") (pintype "passive"))
    )
    (net (code "89") (name "/USART3_TX") (class "Default")
      (node (ref "P1") (pin "4") (pinfunction "4_4") (pintype "passive"))
      (node (ref "R2") (pin "2") (pintype "passive"))
      (node (ref "U6") (pin "2") (pinfunction "2_2") (pintype "passive"))
    )
    (net (code "90") (name "/USART6_RX") (class "Default")
      (node (ref "P2") (pin "3") (pinfunction "3_3") (pintype "passive"))
      (node (ref "R8") (pin "2") (pintype "passive"))
      (node (ref "U5") (pin "1") (pinfunction "1_1") (pintype "passive"))
    )
    (net (code "91") (name "/USART6_TX") (class "Default")
      (node (ref "P2") (pin "4") (pinfunction "4_4") (pintype "passive"))
      (node (ref "R6") (pin "2") (pintype "passive"))
      (node (ref "U5") (pin "2") (pinfunction "2_2") (pintype "passive"))
    )
    (net (code "92") (name "/VCAP_1") (class "Default")
      (node (ref "C17") (pin "2") (pinfunction "2_2") (pintype "passive"))
      (node (ref "U1") (pin "49") (pinfunction "VCAP_1_49") (pintype "passive"))
    )
    (net (code "93") (name "/VCAP_2") (class "Default")
      (node (ref "C16") (pin "2") (pinfunction "2_2") (pintype "passive"))
      (node (ref "U1") (pin "73") (pinfunction "VCAP_2_73") (pintype "passive"))
    )
    (net (code "94") (name "3V3") (class "Default")
      (node (ref "*1") (pin "3") (pinfunction "VCC_3") (pintype "passive"))
      (node (ref "*2") (pin "3") (pinfunction "VCC_3") (pintype "passive"))
      (node (ref "*3") (pin "36") (pinfunction "36_36") (pintype "passive"))
      (node (ref "*4") (pin "33") (pinfunction "33_33") (pintype "passive"))
      (node (ref "*4") (pin "35") (pinfunction "35_35") (pintype "passive"))
      (node (ref "C12") (pin "1") (pinfunction "1_1") (pintype "passive"))
      (node (ref "C13") (pin "1") (pinfunction "1_1") (pintype "passive"))
      (node (ref "C14") (pin "1") (pinfunction "1_1") (pintype "passive"))
      (node (ref "C15") (pin "1") (pinfunction "1_1") (pintype "passive"))
      (node (ref "C21") (pin "2") (pinfunction "2_2") (pintype "passive"))
      (node (ref "C22") (pin "2") (pinfunction "2_2") (pintype "passive"))
      (node (ref "C23") (pin "2") (pinfunction "2_2") (pintype "passive"))
      (node (ref "C24") (pin "2") (pinfunction "2_2") (pintype "passive"))
      (node (ref "C25") (pin "2") (pinfunction "2_2") (pintype "passive"))
      (node (ref "C26") (pin "2") (pinfunction "2_2") (pintype "passive"))
      (node (ref "C27") (pin "2") (pinfunction "2_2") (pintype "passive"))
      (node (ref "C30") (pin "2") (pinfunction "2_2") (pintype "passive"))
      (node (ref "C31") (pin "1") (pinfunction "1_1") (pintype "passive"))
      (node (ref "C4") (pin "1") (pinfunction "1_1") (pintype "passive"))
      (node (ref "C5") (pin "1") (pinfunction "1_1") (pintype "passive"))
      (node (ref "C7") (pin "1") (pinfunction "1_1") (pintype "passive"))
      (node (ref "C8") (pin "1") (pinfunction "1_1") (pintype "passive"))
      (node (ref "P10") (pin "1") (pinfunction "1_1") (pintype "passive"))
      (node (ref "P5") (pin "1") (pinfunction "1_1") (pintype "passive"))
      (node (ref "P9") (pin "1") (pinfunction "1_1") (pintype "passive"))
      (node (ref "R13") (pin "2") (pinfunction "2_2") (pintype "passive"))
      (node (ref "R17") (pin "1") (pinfunction "1_1") (pintype "passive"))
      (node (ref "R22") (pin "1") (pinfunction "1_1") (pintype "passive"))
      (node (ref "R23") (pin "1") (pinfunction "1_1") (pintype "passive"))
      (node (ref "U1") (pin "100") (pinfunction "VDD_100") (pintype "power_in"))
      (node (ref "U1") (pin "11") (pinfunction "VDD_11") (pintype "passive"))
      (node (ref "U1") (pin "19") (pinfunction "VDD_19") (pintype "passive"))
      (node (ref "U1") (pin "22") (pinfunction "VDDA_22") (pintype "passive"))
      (node (ref "U1") (pin "28") (pinfunction "VDD_28") (pintype "passive"))
      (node (ref "U1") (pin "50") (pinfunction "VDD_50") (pintype "passive"))
      (node (ref "U1") (pin "6") (pinfunction "VBAT_6") (pintype "passive"))
      (node (ref "U1") (pin "75") (pinfunction "VDD_75") (pintype "passive"))
      (node (ref "U3") (pin "2") (pinfunction "OUT_2") (pintype "passive"))
      (node (ref "U4") (pin "16") (pinfunction "VCC_16") (pintype "passive"))
    )
    (net (code "95") (name "GND") (class "Default")
      (node (ref "*1") (pin "2") (pinfunction "GND_2") (pintype "passive"))
      (node (ref "*2") (pin "2") (pinfunction "GND_2") (pintype "passive"))
      (node (ref "*3") (pin "35") (pinfunction "35_35") (pintype "passive"))
      (node (ref "*4") (pin "30") (pinfunction "30_30") (pintype "passive"))
      (node (ref "*4") (pin "31") (pinfunction "31_31") (pintype "passive"))
      (node (ref "*4") (pin "32") (pinfunction "32_32") (pintype "passive"))
      (node (ref "C1") (pin "1") (pinfunction "1_1") (pintype "passive"))
      (node (ref "C11") (pin "2") (pinfunction "2_2") (pintype "passive"))
      (node (ref "C12") (pin "2") (pinfunction "2_2") (pintype "passive"))
      (node (ref "C13") (pin "2") (pinfunction "2_2") (pintype "passive"))
      (node (ref "C14") (pin "2") (pinfunction "2_2") (pintype "passive"))
      (node (ref "C15") (pin "2") (pinfunction "2_2") (pintype "passive"))
      (node (ref "C16") (pin "1") (pinfunction "1_1") (pintype "passive"))
      (node (ref "C17") (pin "1") (pinfunction "1_1") (pintype "passive"))
      (node (ref "C2") (pin "2") (pinfunction "2_2") (pintype "passive"))
      (node (ref "C20") (pin "2") (pinfunction "2_2") (pintype "passive"))
      (node (ref "C21") (pin "1") (pinfunction "1_1") (pintype "passive"))
      (node (ref "C22") (pin "1") (pinfunction "1_1") (pintype "passive"))
      (node (ref "C23") (pin "1") (pinfunction "1_1") (pintype "passive"))
      (node (ref "C24") (pin "1") (pinfunction "1_1") (pintype "passive"))
      (node (ref "C25") (pin "1") (pinfunction "1_1") (pintype "passive"))
      (node (ref "C26") (pin "1") (pinfunction "1_1") (pintype "passive"))
      (node (ref "C27") (pin "1") (pinfunction "1_1") (pintype "passive"))
      (node (ref "C28") (pin "2") (pinfunction "2_2") (pintype "passive"))
      (node (ref "C29") (pin "2") (pinfunction "2_2") (pintype "passive"))
      (node (ref "C3") (pin "2") (pinfunction "2_2") (pintype "passive"))
      (node (ref "C30") (pin "1") (pinfunction "1_1") (pintype "passive"))
      (node (ref "C4") (pin "2") (pinfunction "2_2") (pintype "passive"))
      (node (ref "C5") (pin "2") (pinfunction "2_2") (pintype "passive"))
      (node (ref "C6") (pin "1") (pinfunction "1_1") (pintype "passive"))
      (node (ref "C7") (pin "2") (pinfunction "2_2") (pintype "passive"))
      (node (ref "D1") (pin "K") (pinfunction "2_K") (pintype "passive"))
      (node (ref "D2") (pin "K") (pinfunction "2_K") (pintype "passive"))
      (node (ref "D4") (pin "K") (pinfunction "2_K") (pintype "passive"))
      (node (ref "P1") (pin "2") (pinfunction "2_2") (pintype "passive"))
      (node (ref "P11") (pin "2") (pinfunction "2_2") (pintype "passive"))
      (node (ref "P2") (pin "2") (pinfunction "2_2") (pintype "passive"))
      (node (ref "P3") (pin "2") (pinfunction "2_2") (pintype "passive"))
      (node (ref "P4") (pin "2") (pinfunction "2_2") (pintype "passive"))
      (node (ref "P5") (pin "2") (pinfunction "2_2") (pintype "passive"))
      (node (ref "P7") (pin "1") (pinfunction "1_1") (pintype "passive"))
      (node (ref "Q1") (pin "2") (pinfunction "E_2") (pintype "passive"))
      (node (ref "R10") (pin "2") (pinfunction "2_2") (pintype "passive"))
      (node (ref "R12") (pin "2") (pinfunction "2_2") (pintype "passive"))
      (node (ref "R14") (pin "2") (pinfunction "2_2") (pintype "passive"))
      (node (ref "R19") (pin "1") (pinfunction "1_1") (pintype "passive"))
      (node (ref "R21") (pin "1") (pinfunction "1_1") (pintype "passive"))
      (node (ref "R9") (pin "1") (pinfunction "1_1") (pintype "passive"))
      (node (ref "T1") (pin "3") (pinfunction "3_3") (pintype "passive"))
      (node (ref "T2") (pin "3") (pinfunction "3_3") (pintype "passive"))
      (node (ref "U1") (pin "10") (pinfunction "VSS_10") (pintype "power_in"))
      (node (ref "U1") (pin "20") (pinfunction "VSS_20") (pintype "power_in"))
      (node (ref "U1") (pin "27") (pinfunction "VSS_27") (pintype "power_in"))
      (node (ref "U1") (pin "74") (pinfunction "VSS_74") (pintype "passive"))
      (node (ref "U1") (pin "99") (pinfunction "VSS_99") (pintype "power_in"))
      (node (ref "U2") (pin "2") (pinfunction "GND_2") (pintype "passive"))
      (node (ref "U3") (pin "1") (pinfunction "GND_1") (pintype "passive"))
      (node (ref "U4") (pin "15") (pinfunction "GND_15") (pintype "passive"))
      (node (ref "U5") (pin "3") (pinfunction "3_3") (pintype "passive"))
      (node (ref "U6") (pin "3") (pinfunction "3_3") (pintype "passive"))
    )
    (net (code "96") (name "Net-(*1-RS)") (class "Default")
      (node (ref "*1") (pin "8") (pinfunction "RS_8") (pintype "passive"))
      (node (ref "R10") (pin "1") (pinfunction "1_1") (pintype "passive"))
    )
    (net (code "97") (name "Net-(*2-RS)") (class "Default")
      (node (ref "*2") (pin "8") (pinfunction "RS_8") (pintype "passive"))
      (node (ref "R14") (pin "1") (pinfunction "1_1") (pintype "passive"))
    )
    (net (code "98") (name "Net-(C18-Pad1)") (class "Default")
      (node (ref "C18") (pin "1") (pinfunction "1_1") (pintype "passive"))
      (node (ref "C19") (pin "1") (pinfunction "1_1") (pintype "passive"))
      (node (ref "R9") (pin "2") (pinfunction "2_2") (pintype "passive"))
    )
    (net (code "99") (name "Net-(D1-1)") (class "Default")
      (node (ref "D1") (pin "A") (pinfunction "1_A") (pintype "passive"))
      (node (ref "R16") (pin "2") (pinfunction "2_2") (pintype "passive"))
    )
    (net (code "100") (name "Net-(D2-1)") (class "Default")
      (node (ref "D2") (pin "A") (pinfunction "1_A") (pintype "passive"))
      (node (ref "R17") (pin "2") (pinfunction "2_2") (pintype "passive"))
    )
    (net (code "101") (name "Net-(D3-1)") (class "Default")
      (node (ref "D3") (pin "A") (pinfunction "1_A") (pintype "passive"))
      (node (ref "R22") (pin "2") (pinfunction "2_2") (pintype "passive"))
    )
    (net (code "102") (name "Net-(D4-1)") (class "Default")
      (node (ref "D4") (pin "A") (pinfunction "1_A") (pintype "passive"))
      (node (ref "R18") (pin "1") (pinfunction "1_1") (pintype "passive"))
    )
    (net (code "103") (name "Net-(D5-1)") (class "Default")
      (node (ref "D5") (pin "A") (pinfunction "1_A") (pintype "passive"))
      (node (ref "R23") (pin "2") (pinfunction "2_2") (pintype "passive"))
    )
    (net (code "104") (name "Net-(J1-Pad2)") (class "Default")
      (node (ref "J1") (pin "2") (pinfunction "2_2") (pintype "passive"))
      (node (ref "R11") (pin "1") (pinfunction "1_1") (pintype "passive"))
    )
    (net (code "105") (name "Net-(J2-Pad1)") (class "Default")
      (node (ref "J2") (pin "1") (pinfunction "1_1") (pintype "passive"))
      (node (ref "R15") (pin "1") (pinfunction "1_1") (pintype "passive"))
    )
    (net (code "106") (name "Net-(P6-Pad1)") (class "Default")
      (node (ref "P6") (pin "1") (pinfunction "1_1") (pintype "passive"))
      (node (ref "P6") (pin "3") (pinfunction "3_3") (pintype "passive"))
      (node (ref "T1") (pin "2") (pinfunction "2_2") (pintype "passive"))
      (node (ref "U7") (pin "2") (pinfunction "2_2") (pintype "passive"))
    )
    (net (code "107") (name "Net-(P6-Pad2)") (class "Default")
      (node (ref "P6") (pin "2") (pinfunction "2_2") (pintype "passive"))
      (node (ref "P6") (pin "4") (pinfunction "4_4") (pintype "passive"))
      (node (ref "T1") (pin "1") (pinfunction "1_1") (pintype "passive"))
      (node (ref "U7") (pin "3") (pinfunction "3_3") (pintype "passive"))
    )
    (net (code "108") (name "Net-(P8-Pad1)") (class "Default")
      (node (ref "P8") (pin "1") (pinfunction "1_1") (pintype "passive"))
      (node (ref "P8") (pin "3") (pinfunction "3_3") (pintype "passive"))
      (node (ref "T2") (pin "2") (pinfunction "2_2") (pintype "passive"))
      (node (ref "U8") (pin "2") (pinfunction "2_2") (pintype "passive"))
    )
    (net (code "109") (name "Net-(P8-Pad2)") (class "Default")
      (node (ref "P8") (pin "2") (pinfunction "2_2") (pintype "passive"))
      (node (ref "P8") (pin "4") (pinfunction "4_4") (pintype "passive"))
      (node (ref "T2") (pin "1") (pinfunction "1_1") (pintype "passive"))
      (node (ref "U8") (pin "3") (pinfunction "3_3") (pintype "passive"))
    )
    (net (code "110") (name "Net-(Q1-B)") (class "Default")
      (node (ref "Q1") (pin "1") (pinfunction "B_1") (pintype "passive"))
      (node (ref "R20") (pin "2") (pinfunction "2_2") (pintype "passive"))
    )
    (net (code "111") (name "Net-(Q1-C)") (class "Default")
      (node (ref "P10") (pin "2") (pinfunction "2_2") (pintype "passive"))
      (node (ref "Q1") (pin "3") (pinfunction "C_3") (pintype "passive"))
    )
    (net (code "112") (name "Net-(U4-C1+)") (class "Default")
      (node (ref "C9") (pin "1") (pinfunction "1_1") (pintype "passive"))
      (node (ref "U4") (pin "1") (pinfunction "C1+_1") (pintype "passive"))
    )
    (net (code "113") (name "Net-(U4-C1-)") (class "Default")
      (node (ref "C9") (pin "2") (pinfunction "2_2") (pintype "passive"))
      (node (ref "U4") (pin "3") (pinfunction "C1-_3") (pintype "passive"))
    )
    (net (code "114") (name "Net-(U4-C2+)") (class "Default")
      (node (ref "C10") (pin "1") (pinfunction "1_1") (pintype "passive"))
      (node (ref "U4") (pin "4") (pinfunction "C2+_4") (pintype "passive"))
    )
    (net (code "115") (name "Net-(U4-C2-)") (class "Default")
      (node (ref "C10") (pin "2") (pinfunction "2_2") (pintype "passive"))
      (node (ref "U4") (pin "5") (pinfunction "C2-_5") (pintype "passive"))
    )
    (net (code "116") (name "Net-(U4-R1in)") (class "Default")
      (node (ref "R4") (pin "1") (pintype "passive"))
      (node (ref "U4") (pin "13") (pinfunction "R1in_13") (pintype "passive"))
    )
    (net (code "117") (name "Net-(U4-R1out)") (class "Default")
      (node (ref "R3") (pin "2") (pintype "passive"))
      (node (ref "U4") (pin "12") (pinfunction "R1out_12") (pintype "passive"))
    )
    (net (code "118") (name "Net-(U4-R2in)") (class "Default")
      (node (ref "R8") (pin "1") (pintype "passive"))
      (node (ref "U4") (pin "8") (pinfunction "R2in_8") (pintype "passive"))
    )
    (net (code "119") (name "Net-(U4-R2out)") (class "Default")
      (node (ref "R7") (pin "2") (pintype "passive"))
      (node (ref "U4") (pin "9") (pinfunction "R2out_9") (pintype "passive"))
    )
    (net (code "120") (name "Net-(U4-T1in)") (class "Default")
      (node (ref "R1") (pin "2") (pintype "passive"))
      (node (ref "U4") (pin "11") (pinfunction "T1in_11") (pintype "passive"))
    )
    (net (code "121") (name "Net-(U4-T1out)") (class "Default")
      (node (ref "R2") (pin "1") (pintype "passive"))
      (node (ref "U4") (pin "14") (pinfunction "T1out_14") (pintype "passive"))
    )
    (net (code "122") (name "Net-(U4-T2in)") (class "Default")
      (node (ref "R5") (pin "2") (pintype "passive"))
      (node (ref "U4") (pin "10") (pinfunction "T2in_10") (pintype "passive"))
    )
    (net (code "123") (name "Net-(U4-T2out)") (class "Default")
      (node (ref "R6") (pin "1") (pintype "passive"))
      (node (ref "U4") (pin "7") (pinfunction "T2out_7") (pintype "passive"))
    )
    (net (code "124") (name "Net-(U4-V+)") (class "Default")
      (node (ref "C8") (pin "2") (pinfunction "2_2") (pintype "passive"))
      (node (ref "U4") (pin "2") (pinfunction "V+_2") (pintype "passive"))
    )
    (net (code "125") (name "Net-(U4-V-)") (class "Default")
      (node (ref "C11") (pin "1") (pinfunction "1_1") (pintype "passive"))
      (node (ref "U4") (pin "6") (pinfunction "V-_6") (pintype "passive"))
    )
    (net (code "126") (name "VREF") (class "Default")
      (node (ref "C1") (pin "2") (pinfunction "2_2") (pintype "passive"))
      (node (ref "C18") (pin "2") (pinfunction "2_2") (pintype "passive"))
      (node (ref "C19") (pin "2") (pinfunction "2_2") (pintype "passive"))
      (node (ref "U1") (pin "21") (pinfunction "VREF+_21") (pintype "passive"))
      (node (ref "U2") (pin "5") (pinfunction "Vout_5") (pintype "passive"))
    )
    (net (code "127") (name "unconnected-(*1-SHDN-Pad5)") (class "Default")
      (node (ref "*1") (pin "5") (pinfunction "SHDN_5") (pintype "passive+no_connect"))
    )
    (net (code "128") (name "unconnected-(*2-SHDN-Pad5)") (class "Default")
      (node (ref "*2") (pin "5") (pinfunction "SHDN_5") (pintype "passive+no_connect"))
    )
    (net (code "129") (name "unconnected-(U1-OSC32_IN-Pad8)") (class "Default")
      (node (ref "U1") (pin "8") (pinfunction "OSC32_IN_8") (pintype "passive"))
    )
    (net (code "130") (name "unconnected-(U1-OSC32_OUT-Pad9)") (class "Default")
      (node (ref "U1") (pin "9") (pinfunction "OSC32_OUT_9") (pintype "passive"))
    )
    (net (code "131") (name "unconnected-(U2-REF-Pad1)") (class "Default")
      (node (ref "U2") (pin "1") (pinfunction "REF_1") (pintype "passive+no_connect"))
    )
  )
)
